# mask_supply.net
KiCad netlist of a schematic drawn in EAGLE
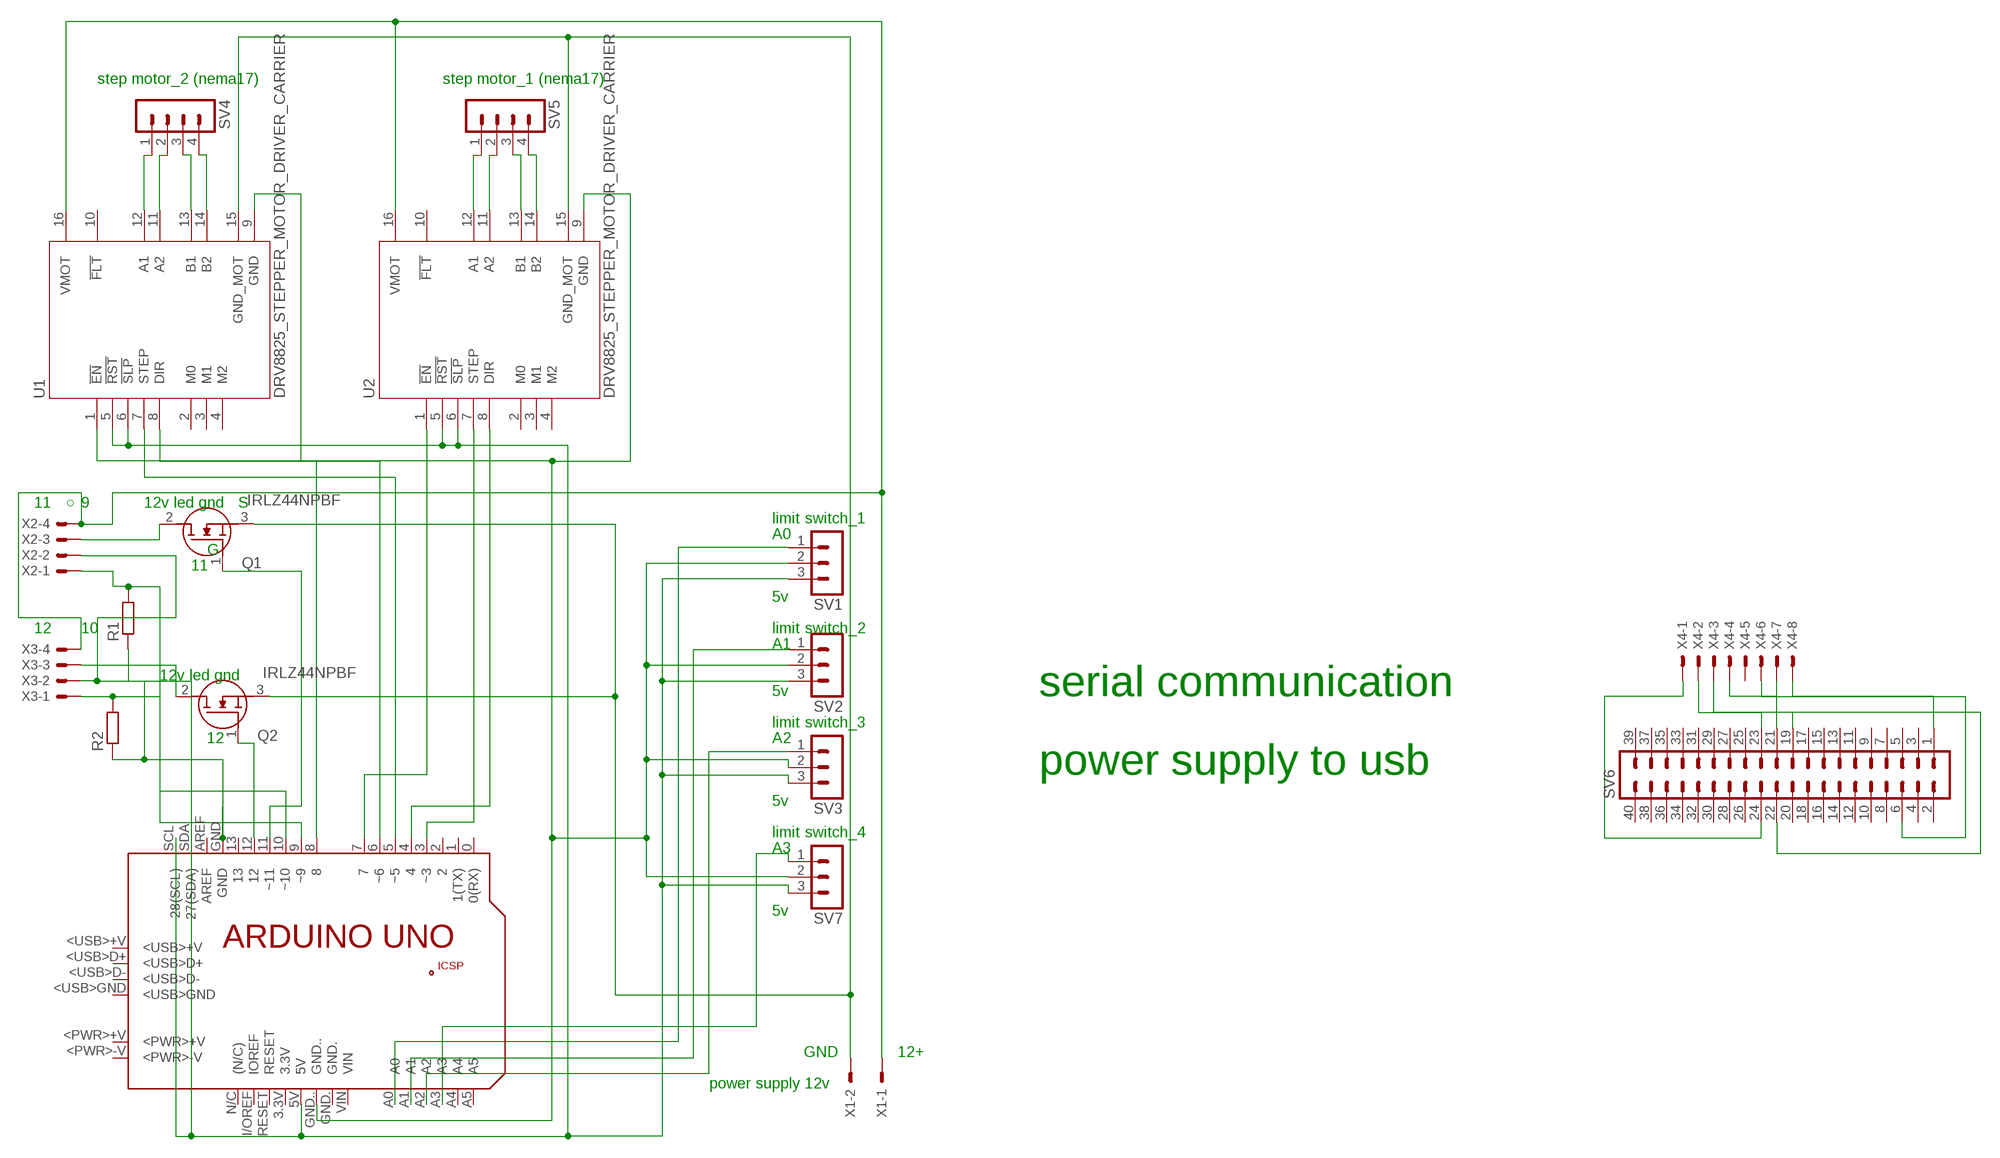
[diagram p0: schematic, sheet 1]

(export (version "E")
  (design (tool "Eeschema 10.0.6"))
  (components
    (comp (ref "PCB1")
      (value "ARDUINO_UNO")
      (footprint "eagle-import:ARDUINO_UNO")
      (libsource (lib "eagle-import") (part "ARDUINO_UNO"))
    )
    (comp (ref "Q1")
      (value "IRLZ44NPBF")
      (footprint "eagle-import:TO254P469X1042X1967-3P")
      (fields (field (name "RS_PART_NUMBER") "0301035"))
      (libsource (lib "eagle-import") (part "IRLZ44NPBF"))
    )
    (comp (ref "Q2")
      (value "IRLZ44NPBF")
      (footprint "eagle-import:TO254P469X1042X1967-3P")
      (fields (field (name "RS_PART_NUMBER") "0301035"))
      (libsource (lib "eagle-import") (part "IRLZ44NPBF"))
    )
    (comp (ref "R1")
      (value "R-EU_0309/10")
      (footprint "eagle-import:0309_10")
      (libsource (lib "eagle-import") (part "R-EU_0309/10"))
    )
    (comp (ref "R2")
      (value "R-EU_0309/10")
      (footprint "eagle-import:0309_10")
      (libsource (lib "eagle-import") (part "R-EU_0309/10"))
    )
    (comp (ref "SV1")
      (value "MA03-1")
      (footprint "eagle-import:MA03-1")
      (libsource (lib "eagle-import") (part "MA03-1"))
    )
    (comp (ref "SV2")
      (value "MA03-1")
      (footprint "eagle-import:MA03-1")
      (libsource (lib "eagle-import") (part "MA03-1"))
    )
    (comp (ref "SV3")
      (value "MA03-1")
      (footprint "eagle-import:MA03-1")
      (libsource (lib "eagle-import") (part "MA03-1"))
    )
    (comp (ref "SV4")
      (value "MA04-1")
      (footprint "eagle-import:MA04-1")
      (libsource (lib "eagle-import") (part "MA04-1"))
    )
    (comp (ref "SV5")
      (value "MA04-1")
      (footprint "eagle-import:MA04-1")
      (libsource (lib "eagle-import") (part "MA04-1"))
    )
    (comp (ref "SV6")
      (value "MA20-2")
      (footprint "eagle-import:MA20-2")
      (libsource (lib "eagle-import") (part "MA20-2"))
    )
    (comp (ref "SV7")
      (value "MA03-1")
      (footprint "eagle-import:MA03-1")
      (libsource (lib "eagle-import") (part "MA03-1"))
    )
    (comp (ref "U1")
      (value "DRV8825_STEPPER_MOTOR_DRIVER_CARRIER")
      (footprint "eagle-import:IC_DRV8825_STEPPER_MOTOR_DRIVER_CARRIER")
      (fields (field (name "MF") "Pololu") (field (name "MP") "DRV8825 STEPPER MOTOR DRIVER CARRIER"))
      (libsource (lib "eagle-import") (part "DRV8825_STEPPER_MOTOR_DRIVER_CARRIER"))
    )
    (comp (ref "U2")
      (value "DRV8825_STEPPER_MOTOR_DRIVER_CARRIER")
      (footprint "eagle-import:IC_DRV8825_STEPPER_MOTOR_DRIVER_CARRIER")
      (fields (field (name "MF") "Pololu") (field (name "MP") "DRV8825 STEPPER MOTOR DRIVER CARRIER"))
      (libsource (lib "eagle-import") (part "DRV8825_STEPPER_MOTOR_DRIVER_CARRIER"))
    )
    (comp (ref "X1")
      (value "KK-156-2")
      (footprint "eagle-import:KK-156-2")
      (fields (field (name "MF") "MOLEX"))
      (libsource (lib "eagle-import") (part "KK-156-2"))
    )
    (comp (ref "X2")
      (value "KK-156-4")
      (footprint "eagle-import:KK-156-4")
      (fields (field (name "MF") "MOLEX"))
      (libsource (lib "eagle-import") (part "KK-156-4"))
    )
    (comp (ref "X3")
      (value "KK-156-4")
      (footprint "eagle-import:KK-156-4")
      (fields (field (name "MF") "MOLEX"))
      (libsource (lib "eagle-import") (part "KK-156-4"))
    )
    (comp (ref "X4")
      (value "KK-156-8")
      (footprint "eagle-import:KK-156-8")
      (fields (field (name "MF") "MOLEX"))
      (libsource (lib "eagle-import") (part "KK-156-8"))
    )
  )
  (nets
    (net (code "1") (name "Net-(PCB1-27(SDA))") (class "Default")
      (node (ref "PCB1") (pin "5V") (pinfunction "5V_5V") (pintype "bidirectional"))
      (node (ref "PCB1") (pin "SCL") (pinfunction "28(SCL)_SCL") (pintype "bidirectional"))
      (node (ref "PCB1") (pin "SDA") (pinfunction "27(SDA)_SDA") (pintype "bidirectional"))
      (node (ref "SV1") (pin "3") (pinfunction "3_3") (pintype "passive"))
      (node (ref "SV2") (pin "3") (pinfunction "3_3") (pintype "passive"))
      (node (ref "SV3") (pin "3") (pinfunction "3_3") (pintype "passive"))
      (node (ref "SV7") (pin "3") (pinfunction "3_3") (pintype "passive"))
      (node (ref "U1") (pin "5") (pinfunction "~{RST}_5") (pintype "input"))
      (node (ref "U1") (pin "6") (pinfunction "~{SLP}_6") (pintype "input"))
      (node (ref "U2") (pin "5") (pinfunction "~{RST}_5") (pintype "input"))
      (node (ref "U2") (pin "6") (pinfunction "~{SLP}_6") (pintype "input"))
      (node (ref "X2") (pin "2") (pinfunction "S_2") (pintype "passive"))
      (node (ref "X3") (pin "2") (pinfunction "S_2") (pintype "passive"))
    )
    (net (code "2") (name "Net-(PCB1-PadA0)") (class "Default")
      (node (ref "PCB1") (pin "A0") (pinfunction "A0_A0") (pintype "bidirectional"))
      (node (ref "SV1") (pin "1") (pinfunction "1_1") (pintype "passive"))
    )
    (net (code "3") (name "Net-(PCB1-PadA1)") (class "Default")
      (node (ref "PCB1") (pin "A1") (pinfunction "A1_A1") (pintype "bidirectional"))
      (node (ref "SV2") (pin "1") (pinfunction "1_1") (pintype "passive"))
    )
    (net (code "4") (name "Net-(PCB1-PadA2)") (class "Default")
      (node (ref "PCB1") (pin "A2") (pinfunction "A2_A2") (pintype "bidirectional"))
      (node (ref "SV3") (pin "1") (pinfunction "1_1") (pintype "passive"))
    )
    (net (code "5") (name "Net-(PCB1-PadA3)") (class "Default")
      (node (ref "PCB1") (pin "A3") (pinfunction "A3_A3") (pintype "bidirectional"))
      (node (ref "SV7") (pin "1") (pinfunction "1_1") (pintype "passive"))
    )
    (net (code "6") (name "Net-(PCB1-PadGND)") (class "Default")
      (node (ref "PCB1") (pin "GND") (pinfunction "GND_GND") (pintype "bidirectional"))
      (node (ref "R1") (pin "1") (pinfunction "1_1") (pintype "passive"))
      (node (ref "R2") (pin "1") (pinfunction "1_1") (pintype "passive"))
    )
    (net (code "7") (name "Net-(PCB1-~{3})") (class "Default")
      (node (ref "PCB1") (pin "3") (pinfunction "~{3}_3") (pintype "bidirectional"))
      (node (ref "U2") (pin "7") (pinfunction "STEP_7") (pintype "input"))
    )
    (net (code "8") (name "Net-(PCB1-~{5})") (class "Default")
      (node (ref "PCB1") (pin "5") (pinfunction "~{5}_5") (pintype "bidirectional"))
      (node (ref "U1") (pin "7") (pinfunction "STEP_7") (pintype "input"))
    )
    (net (code "9") (name "Net-(PCB1-~{6})") (class "Default")
      (node (ref "PCB1") (pin "6") (pinfunction "~{6}_6") (pintype "bidirectional"))
      (node (ref "U1") (pin "8") (pinfunction "DIR_8") (pintype "input"))
    )
    (net (code "10") (name "Net-(PCB1-~{9})") (class "Default")
      (node (ref "PCB1") (pin "9") (pinfunction "~{9}_9") (pintype "bidirectional"))
      (node (ref "R1") (pin "2") (pinfunction "2_2") (pintype "passive"))
      (node (ref "X2") (pin "1") (pinfunction "S_1") (pintype "passive"))
    )
    (net (code "11") (name "Net-(PCB1-~{10})") (class "Default")
      (node (ref "PCB1") (pin "10") (pinfunction "~{10}_10") (pintype "bidirectional"))
      (node (ref "R2") (pin "2") (pinfunction "2_2") (pintype "passive"))
      (node (ref "X3") (pin "1") (pinfunction "S_1") (pintype "passive"))
    )
    (net (code "12") (name "Net-(PCB1-~{11})") (class "Default")
      (node (ref "PCB1") (pin "11") (pinfunction "~{11}_11") (pintype "bidirectional"))
      (node (ref "Q1") (pin "1") (pinfunction "G_1") (pintype "input"))
    )
    (net (code "13") (name "Net-(Q1-D)") (class "Default")
      (node (ref "Q1") (pin "2") (pinfunction "D_2") (pintype "output"))
      (node (ref "X2") (pin "3") (pinfunction "S_3") (pintype "passive"))
    )
    (net (code "14") (name "Net-(Q1-S)") (class "Default")
      (node (ref "Q1") (pin "3") (pinfunction "S_3") (pintype "input"))
      (node (ref "Q2") (pin "3") (pinfunction "S_3") (pintype "input"))
      (node (ref "U1") (pin "15") (pinfunction "GND_MOT_15") (pintype "power_in"))
      (node (ref "U2") (pin "15") (pinfunction "GND_MOT_15") (pintype "power_in"))
      (node (ref "X1") (pin "2") (pinfunction "S_2") (pintype "passive"))
    )
    (net (code "15") (name "Net-(Q2-D)") (class "Default")
      (node (ref "Q2") (pin "2") (pinfunction "D_2") (pintype "output"))
      (node (ref "X3") (pin "3") (pinfunction "S_3") (pintype "passive"))
    )
    (net (code "16") (name "Net-(Q2-G)") (class "Default")
      (node (ref "PCB1") (pin "12") (pinfunction "12_12") (pintype "bidirectional"))
      (node (ref "Q2") (pin "1") (pinfunction "G_1") (pintype "input"))
    )
    (net (code "17") (name "Net-(U1-A1)") (class "Default")
      (node (ref "SV4") (pin "1") (pinfunction "1_1") (pintype "passive"))
      (node (ref "U1") (pin "12") (pinfunction "A1_12") (pintype "output"))
    )
    (net (code "18") (name "Net-(U1-A2)") (class "Default")
      (node (ref "SV4") (pin "2") (pinfunction "2_2") (pintype "passive"))
      (node (ref "U1") (pin "11") (pinfunction "A2_11") (pintype "output"))
    )
    (net (code "19") (name "Net-(U1-B1)") (class "Default")
      (node (ref "SV4") (pin "3") (pinfunction "3_3") (pintype "passive"))
      (node (ref "U1") (pin "13") (pinfunction "B1_13") (pintype "output"))
    )
    (net (code "20") (name "Net-(U1-B2)") (class "Default")
      (node (ref "SV4") (pin "4") (pinfunction "4_4") (pintype "passive"))
      (node (ref "U1") (pin "14") (pinfunction "B2_14") (pintype "output"))
    )
    (net (code "21") (name "Net-(U1-GND)") (class "Default")
      (node (ref "PCB1") (pin "GND..") (pinfunction "GND.._GND..") (pintype "bidirectional"))
      (node (ref "SV1") (pin "2") (pinfunction "2_2") (pintype "passive"))
      (node (ref "SV2") (pin "2") (pinfunction "2_2") (pintype "passive"))
      (node (ref "SV3") (pin "2") (pinfunction "2_2") (pintype "passive"))
      (node (ref "SV7") (pin "2") (pinfunction "2_2") (pintype "passive"))
      (node (ref "U1") (pin "9") (pinfunction "GND_9") (pintype "power_in"))
      (node (ref "U2") (pin "9") (pinfunction "GND_9") (pintype "power_in"))
    )
    (net (code "22") (name "Net-(U1-VMOT)") (class "Default")
      (node (ref "U1") (pin "16") (pinfunction "VMOT_16") (pintype "power_in"))
      (node (ref "U2") (pin "16") (pinfunction "VMOT_16") (pintype "power_in"))
      (node (ref "X1") (pin "1") (pinfunction "S_1") (pintype "passive"))
      (node (ref "X2") (pin "4") (pinfunction "S_4") (pintype "passive"))
      (node (ref "X3") (pin "4") (pinfunction "S_4") (pintype "passive"))
    )
    (net (code "23") (name "Net-(U1-~{EN})") (class "Default")
      (node (ref "PCB1") (pin "8") (pinfunction "8_8") (pintype "bidirectional"))
      (node (ref "U1") (pin "1") (pinfunction "~{EN}_1") (pintype "input"))
    )
    (net (code "24") (name "Net-(U2-A1)") (class "Default")
      (node (ref "SV5") (pin "1") (pinfunction "1_1") (pintype "passive"))
      (node (ref "U2") (pin "12") (pinfunction "A1_12") (pintype "output"))
    )
    (net (code "25") (name "Net-(U2-A2)") (class "Default")
      (node (ref "SV5") (pin "2") (pinfunction "2_2") (pintype "passive"))
      (node (ref "U2") (pin "11") (pinfunction "A2_11") (pintype "output"))
    )
    (net (code "26") (name "Net-(U2-B1)") (class "Default")
      (node (ref "SV5") (pin "3") (pinfunction "3_3") (pintype "passive"))
      (node (ref "U2") (pin "13") (pinfunction "B1_13") (pintype "output"))
    )
    (net (code "27") (name "Net-(U2-B2)") (class "Default")
      (node (ref "SV5") (pin "4") (pinfunction "4_4") (pintype "passive"))
      (node (ref "U2") (pin "14") (pinfunction "B2_14") (pintype "output"))
    )
    (net (code "28") (name "Net-(U2-DIR)") (class "Default")
      (node (ref "PCB1") (pin "4") (pinfunction "4_4") (pintype "bidirectional"))
      (node (ref "U2") (pin "8") (pinfunction "DIR_8") (pintype "input"))
    )
    (net (code "29") (name "Net-(U2-~{EN})") (class "Default")
      (node (ref "PCB1") (pin "7") (pinfunction "7_7") (pintype "bidirectional"))
      (node (ref "U2") (pin "1") (pinfunction "~{EN}_1") (pintype "input"))
    )
    (net (code "30") (name "Net-(X4A-S)") (class "Default")
      (node (ref "SV6") (pin "24") (pinfunction "24_24") (pintype "passive"))
      (node (ref "X4") (pin "1") (pinfunction "S_1") (pintype "passive"))
    )
    (net (code "31") (name "Net-(X4B-S)") (class "Default")
      (node (ref "SV6") (pin "23") (pinfunction "23_23") (pintype "passive"))
      (node (ref "X4") (pin "2") (pinfunction "S_2") (pintype "passive"))
    )
    (net (code "32") (name "Net-(X4C-S)") (class "Default")
      (node (ref "SV6") (pin "19") (pinfunction "19_19") (pintype "passive"))
      (node (ref "X4") (pin "3") (pinfunction "S_3") (pintype "passive"))
    )
    (net (code "33") (name "Net-(X4D-S)") (class "Default")
      (node (ref "SV6") (pin "21") (pinfunction "21_21") (pintype "passive"))
      (node (ref "X4") (pin "4") (pinfunction "S_4") (pintype "passive"))
    )
    (net (code "34") (name "Net-(X4F-S)") (class "Default")
      (node (ref "SV6") (pin "6") (pinfunction "6_6") (pintype "passive"))
      (node (ref "X4") (pin "6") (pinfunction "S_6") (pintype "passive"))
    )
    (net (code "35") (name "Net-(X4G-S)") (class "Default")
      (node (ref "SV6") (pin "22") (pinfunction "22_22") (pintype "passive"))
      (node (ref "X4") (pin "7") (pinfunction "S_7") (pintype "passive"))
    )
    (net (code "36") (name "Net-(X4H-S)") (class "Default")
      (node (ref "SV6") (pin "1") (pinfunction "1_1") (pintype "passive"))
      (node (ref "X4") (pin "8") (pinfunction "S_8") (pintype "passive"))
    )
    (net (code "37") (name "unconnected-(PCB1-(N{slash}C)-PadN{slash}C)") (class "Default")
      (node (ref "PCB1") (pin "N/C") (pinfunction "(N/C)_N/C") (pintype "bidirectional"))
    )
    (net (code "38") (name "unconnected-(PCB1-0(RX)-Pad0)") (class "Default")
      (node (ref "PCB1") (pin "0") (pinfunction "0(RX)_0") (pintype "bidirectional"))
    )
    (net (code "39") (name "unconnected-(PCB1-1(TX)-Pad1)") (class "Default")
      (node (ref "PCB1") (pin "1") (pinfunction "1(TX)_1") (pintype "bidirectional"))
    )
    (net (code "40") (name "unconnected-(PCB1-IOREF-PadI{slash}OREF)") (class "Default")
      (node (ref "PCB1") (pin "I/OREF") (pinfunction "IOREF_I/OREF") (pintype "bidirectional"))
    )
    (net (code "41") (name "unconnected-(PCB1-Pad+5V)") (class "Default")
      (node (ref "PCB1") (pin "+5V") (pinfunction "+5V_+5V") (pintype "bidirectional"))
    )
    (net (code "42") (name "unconnected-(PCB1-Pad2)") (class "Default")
      (node (ref "PCB1") (pin "2") (pinfunction "2_2") (pintype "bidirectional"))
    )
    (net (code "43") (name "unconnected-(PCB1-Pad3.3V)") (class "Default")
      (node (ref "PCB1") (pin "3.3V") (pinfunction "3.3V_3.3V") (pintype "bidirectional"))
    )
    (net (code "44") (name "unconnected-(PCB1-Pad13)") (class "Default")
      (node (ref "PCB1") (pin "13") (pinfunction "13_13") (pintype "bidirectional"))
    )
    (net (code "45") (name "unconnected-(PCB1-Pad<PWR>+V)") (class "Default")
      (node (ref "PCB1") (pin "<PWR>+V") (pinfunction "<PWR>+V_<PWR>+V") (pintype "bidirectional"))
    )
    (net (code "46") (name "unconnected-(PCB1-Pad<PWR>-V)") (class "Default")
      (node (ref "PCB1") (pin "<PWR>-V") (pinfunction "<PWR>-V_<PWR>-V") (pintype "bidirectional"))
    )
    (net (code "47") (name "unconnected-(PCB1-Pad<USB>+V)") (class "Default")
      (node (ref "PCB1") (pin "<USB>+V") (pinfunction "<USB>+V_<USB>+V") (pintype "bidirectional"))
    )
    (net (code "48") (name "unconnected-(PCB1-Pad<USB>D+)") (class "Default")
      (node (ref "PCB1") (pin "<USB>D+") (pinfunction "<USB>D+_<USB>D+") (pintype "bidirectional"))
    )
    (net (code "49") (name "unconnected-(PCB1-Pad<USB>D-)") (class "Default")
      (node (ref "PCB1") (pin "<USB>D-") (pinfunction "<USB>D-_<USB>D-") (pintype "bidirectional"))
    )
    (net (code "50") (name "unconnected-(PCB1-Pad<USB>GND)") (class "Default")
      (node (ref "PCB1") (pin "<USB>GND") (pinfunction "<USB>GND_<USB>GND") (pintype "bidirectional"))
    )
    (net (code "51") (name "unconnected-(PCB1-PadA4)") (class "Default")
      (node (ref "PCB1") (pin "A4") (pinfunction "A4_A4") (pintype "bidirectional"))
    )
    (net (code "52") (name "unconnected-(PCB1-PadA5)") (class "Default")
      (node (ref "PCB1") (pin "A5") (pinfunction "A5_A5") (pintype "bidirectional"))
    )
    (net (code "53") (name "unconnected-(PCB1-PadAREF)") (class "Default")
      (node (ref "PCB1") (pin "AREF") (pinfunction "AREF_AREF") (pintype "bidirectional"))
    )
    (net (code "54") (name "unconnected-(PCB1-PadGND.)") (class "Default")
      (node (ref "PCB1") (pin "GND.") (pinfunction "GND._GND.") (pintype "bidirectional"))
    )
    (net (code "55") (name "unconnected-(PCB1-PadGND_)") (class "Default")
      (node (ref "PCB1") (pin "GND_") (pinfunction "GND__GND_") (pintype "bidirectional"))
    )
    (net (code "56") (name "unconnected-(PCB1-PadMISO)") (class "Default")
      (node (ref "PCB1") (pin "MISO") (pinfunction "MISO_MISO") (pintype "bidirectional"))
    )
    (net (code "57") (name "unconnected-(PCB1-PadMOSI)") (class "Default")
      (node (ref "PCB1") (pin "MOSI") (pinfunction "MOSI_MOSI") (pintype "bidirectional"))
    )
    (net (code "58") (name "unconnected-(PCB1-PadRESET)") (class "Default")
      (node (ref "PCB1") (pin "RESET") (pinfunction "RESET_RESET") (pintype "bidirectional"))
    )
    (net (code "59") (name "unconnected-(PCB1-PadRESET.)") (class "Default")
      (node (ref "PCB1") (pin "RESET.") (pinfunction "RESET._RESET.") (pintype "bidirectional"))
    )
    (net (code "60") (name "unconnected-(PCB1-PadSCK)") (class "Default")
      (node (ref "PCB1") (pin "SCK") (pinfunction "SCK_SCK") (pintype "bidirectional"))
    )
    (net (code "61") (name "unconnected-(PCB1-PadVIN)") (class "Default")
      (node (ref "PCB1") (pin "VIN") (pinfunction "VIN_VIN") (pintype "bidirectional"))
    )
    (net (code "62") (name "unconnected-(SV6-Pad2)") (class "Default")
      (node (ref "SV6") (pin "2") (pinfunction "2_2") (pintype "passive"))
    )
    (net (code "63") (name "unconnected-(SV6-Pad3)") (class "Default")
      (node (ref "SV6") (pin "3") (pinfunction "3_3") (pintype "passive"))
    )
    (net (code "64") (name "unconnected-(SV6-Pad4)") (class "Default")
      (node (ref "SV6") (pin "4") (pinfunction "4_4") (pintype "passive"))
    )
    (net (code "65") (name "unconnected-(SV6-Pad5)") (class "Default")
      (node (ref "SV6") (pin "5") (pinfunction "5_5") (pintype "passive"))
    )
    (net (code "66") (name "unconnected-(SV6-Pad7)") (class "Default")
      (node (ref "SV6") (pin "7") (pinfunction "7_7") (pintype "passive"))
    )
    (net (code "67") (name "unconnected-(SV6-Pad8)") (class "Default")
      (node (ref "SV6") (pin "8") (pinfunction "8_8") (pintype "passive"))
    )
    (net (code "68") (name "unconnected-(SV6-Pad9)") (class "Default")
      (node (ref "SV6") (pin "9") (pinfunction "9_9") (pintype "passive"))
    )
    (net (code "69") (name "unconnected-(SV6-Pad10)") (class "Default")
      (node (ref "SV6") (pin "10") (pinfunction "10_10") (pintype "passive"))
    )
    (net (code "70") (name "unconnected-(SV6-Pad11)") (class "Default")
      (node (ref "SV6") (pin "11") (pinfunction "11_11") (pintype "passive"))
    )
    (net (code "71") (name "unconnected-(SV6-Pad12)") (class "Default")
      (node (ref "SV6") (pin "12") (pinfunction "12_12") (pintype "passive"))
    )
    (net (code "72") (name "unconnected-(SV6-Pad13)") (class "Default")
      (node (ref "SV6") (pin "13") (pinfunction "13_13") (pintype "passive"))
    )
    (net (code "73") (name "unconnected-(SV6-Pad14)") (class "Default")
      (node (ref "SV6") (pin "14") (pinfunction "14_14") (pintype "passive"))
    )
    (net (code "74") (name "unconnected-(SV6-Pad15)") (class "Default")
      (node (ref "SV6") (pin "15") (pinfunction "15_15") (pintype "passive"))
    )
    (net (code "75") (name "unconnected-(SV6-Pad16)") (class "Default")
      (node (ref "SV6") (pin "16") (pinfunction "16_16") (pintype "passive"))
    )
    (net (code "76") (name "unconnected-(SV6-Pad17)") (class "Default")
      (node (ref "SV6") (pin "17") (pinfunction "17_17") (pintype "passive"))
    )
    (net (code "77") (name "unconnected-(SV6-Pad18)") (class "Default")
      (node (ref "SV6") (pin "18") (pinfunction "18_18") (pintype "passive"))
    )
    (net (code "78") (name "unconnected-(SV6-Pad20)") (class "Default")
      (node (ref "SV6") (pin "20") (pinfunction "20_20") (pintype "passive"))
    )
    (net (code "79") (name "unconnected-(SV6-Pad25)") (class "Default")
      (node (ref "SV6") (pin "25") (pinfunction "25_25") (pintype "passive"))
    )
    (net (code "80") (name "unconnected-(SV6-Pad26)") (class "Default")
      (node (ref "SV6") (pin "26") (pinfunction "26_26") (pintype "passive"))
    )
    (net (code "81") (name "unconnected-(SV6-Pad27)") (class "Default")
      (node (ref "SV6") (pin "27") (pinfunction "27_27") (pintype "passive"))
    )
    (net (code "82") (name "unconnected-(SV6-Pad28)") (class "Default")
      (node (ref "SV6") (pin "28") (pinfunction "28_28") (pintype "passive"))
    )
    (net (code "83") (name "unconnected-(SV6-Pad29)") (class "Default")
      (node (ref "SV6") (pin "29") (pinfunction "29_29") (pintype "passive"))
    )
    (net (code "84") (name "unconnected-(SV6-Pad30)") (class "Default")
      (node (ref "SV6") (pin "30") (pinfunction "30_30") (pintype "passive"))
    )
    (net (code "85") (name "unconnected-(SV6-Pad31)") (class "Default")
      (node (ref "SV6") (pin "31") (pinfunction "31_31") (pintype "passive"))
    )
    (net (code "86") (name "unconnected-(SV6-Pad32)") (class "Default")
      (node (ref "SV6") (pin "32") (pinfunction "32_32") (pintype "passive"))
    )
    (net (code "87") (name "unconnected-(SV6-Pad33)") (class "Default")
      (node (ref "SV6") (pin "33") (pinfunction "33_33") (pintype "passive"))
    )
    (net (code "88") (name "unconnected-(SV6-Pad34)") (class "Default")
      (node (ref "SV6") (pin "34") (pinfunction "34_34") (pintype "passive"))
    )
    (net (code "89") (name "unconnected-(SV6-Pad35)") (class "Default")
      (node (ref "SV6") (pin "35") (pinfunction "35_35") (pintype "passive"))
    )
    (net (code "90") (name "unconnected-(SV6-Pad36)") (class "Default")
      (node (ref "SV6") (pin "36") (pinfunction "36_36") (pintype "passive"))
    )
    (net (code "91") (name "unconnected-(SV6-Pad37)") (class "Default")
      (node (ref "SV6") (pin "37") (pinfunction "37_37") (pintype "passive"))
    )
    (net (code "92") (name "unconnected-(SV6-Pad38)") (class "Default")
      (node (ref "SV6") (pin "38") (pinfunction "38_38") (pintype "passive"))
    )
    (net (code "93") (name "unconnected-(SV6-Pad39)") (class "Default")
      (node (ref "SV6") (pin "39") (pinfunction "39_39") (pintype "passive"))
    )
    (net (code "94") (name "unconnected-(SV6-Pad40)") (class "Default")
      (node (ref "SV6") (pin "40") (pinfunction "40_40") (pintype "passive"))
    )
    (net (code "95") (name "unconnected-(U1-M0-Pad2)") (class "Default")
      (node (ref "U1") (pin "2") (pinfunction "M0_2") (pintype "input"))
    )
    (net (code "96") (name "unconnected-(U1-M1-Pad3)") (class "Default")
      (node (ref "U1") (pin "3") (pinfunction "M1_3") (pintype "input"))
    )
    (net (code "97") (name "unconnected-(U1-M2-Pad4)") (class "Default")
      (node (ref "U1") (pin "4") (pinfunction "M2_4") (pintype "input"))
    )
    (net (code "98") (name "unconnected-(U1-~{FLT}-Pad10)") (class "Default")
      (node (ref "U1") (pin "10") (pinfunction "~{FLT}_10") (pintype "output"))
    )
    (net (code "99") (name "unconnected-(U2-M0-Pad2)") (class "Default")
      (node (ref "U2") (pin "2") (pinfunction "M0_2") (pintype "input"))
    )
    (net (code "100") (name "unconnected-(U2-M1-Pad3)") (class "Default")
      (node (ref "U2") (pin "3") (pinfunction "M1_3") (pintype "input"))
    )
    (net (code "101") (name "unconnected-(U2-M2-Pad4)") (class "Default")
      (node (ref "U2") (pin "4") (pinfunction "M2_4") (pintype "input"))
    )
    (net (code "102") (name "unconnected-(U2-~{FLT}-Pad10)") (class "Default")
      (node (ref "U2") (pin "10") (pinfunction "~{FLT}_10") (pintype "output"))
    )
    (net (code "103") (name "unconnected-(X4E-S-Pad5)") (class "Default")
      (node (ref "X4") (pin "5") (pinfunction "S_5") (pintype "passive"))
    )
  )
)
